# Arm.net
KiCad netlist of a schematic drawn in EAGLE
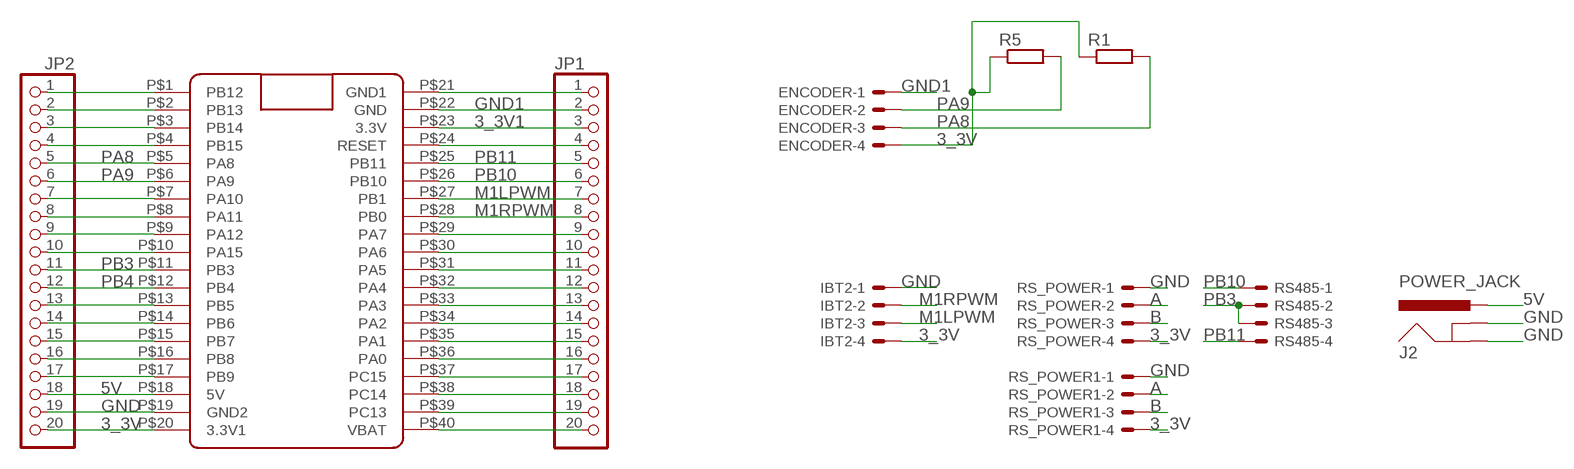
[diagram p0: schematic, sheet 1]

(export (version "E")
  (design (tool "Eeschema 10.0.6"))
  (components
    (comp (ref "ENCODER")
      (value "JST-XH-04-PIN-LONG-PAD")
      (footprint "eagle-import:JST-XH-04-PACKAGE-LONG-PAD")
      (libsource (lib "eagle-import") (part "JST-XH-04-PIN-LONG-PAD"))
    )
    (comp (ref "IBT2")
      (value "JST-XH-04-PIN-LONG-PAD")
      (footprint "eagle-import:JST-XH-04-PACKAGE-LONG-PAD")
      (libsource (lib "eagle-import") (part "JST-XH-04-PIN-LONG-PAD"))
    )
    (comp (ref "J2")
      (value "POWER_JACK")
      (footprint "eagle-import:POWER_JACK")
      (fields (field (name "MPN") "PJ-202A"))
      (libsource (lib "eagle-import") (part "POWER_JACK"))
    )
    (comp (ref "JP1")
      (value "PINHD-1X20")
      (footprint "eagle-import:1X20")
      (libsource (lib "eagle-import") (part "PINHD-1X20"))
    )
    (comp (ref "JP2")
      (value "PINHD-1X20")
      (footprint "eagle-import:1X20")
      (libsource (lib "eagle-import") (part "PINHD-1X20"))
    )
    (comp (ref "R1")
      (value "R-EU_0207/10")
      (footprint "eagle-import:0207_10")
      (libsource (lib "eagle-import") (part "R-EU_0207/10"))
    )
    (comp (ref "R5")
      (value "R-EU_0207/10")
      (footprint "eagle-import:0207_10")
      (libsource (lib "eagle-import") (part "R-EU_0207/10"))
    )
    (comp (ref "RS485")
      (value "JST-XH-04-PIN-LONG-PAD")
      (footprint "eagle-import:JST-XH-04-PACKAGE-LONG-PAD")
      (libsource (lib "eagle-import") (part "JST-XH-04-PIN-LONG-PAD"))
    )
    (comp (ref "RS_POWER")
      (value "JST-XH-04-PIN-LONG-PAD")
      (footprint "eagle-import:JST-XH-04-PACKAGE-LONG-PAD")
      (libsource (lib "eagle-import") (part "JST-XH-04-PIN-LONG-PAD"))
    )
    (comp (ref "RS_POWER1")
      (value "JST-XH-04-PIN-LONG-PAD")
      (footprint "eagle-import:JST-XH-04-PACKAGE-LONG-PAD")
      (libsource (lib "eagle-import") (part "JST-XH-04-PIN-LONG-PAD"))
    )
    (comp (ref "U$1")
      (value "BLUE_PILL")
      (footprint "eagle-import:BLUE_PILL")
      (libsource (lib "eagle-import") (part "BLUE_PILL"))
    )
  )
  (nets
    (net (code "1") (name "/3_3V") (class "Default")
      (node (ref "ENCODER") (pin "4") (pinfunction "S_4") (pintype "passive"))
      (node (ref "IBT2") (pin "4") (pinfunction "S_4") (pintype "passive"))
      (node (ref "JP2") (pin "20") (pinfunction "20_20") (pintype "passive"))
      (node (ref "R1") (pin "1") (pinfunction "1_1") (pintype "passive"))
      (node (ref "R5") (pin "1") (pinfunction "1_1") (pintype "passive"))
      (node (ref "RS_POWER") (pin "4") (pinfunction "S_4") (pintype "passive"))
      (node (ref "RS_POWER1") (pin "4") (pinfunction "S_4") (pintype "passive"))
      (node (ref "U$1") (pin "P$20") (pinfunction "3.3V1_P$20") (pintype "bidirectional"))
    )
    (net (code "2") (name "/3_3V1") (class "Default")
      (node (ref "JP1") (pin "3") (pinfunction "3_3") (pintype "passive"))
      (node (ref "U$1") (pin "P$23") (pinfunction "3.3V_P$23") (pintype "bidirectional"))
    )
    (net (code "3") (name "/5V") (class "Default")
      (node (ref "J2") (pin "PWR") (pinfunction "PWR_PWR") (pintype "bidirectional"))
      (node (ref "JP2") (pin "18") (pinfunction "18_18") (pintype "passive"))
      (node (ref "U$1") (pin "P$18") (pinfunction "5V_P$18") (pintype "bidirectional"))
    )
    (net (code "4") (name "/A") (class "Default")
      (node (ref "RS_POWER") (pin "2") (pinfunction "S_2") (pintype "passive"))
      (node (ref "RS_POWER1") (pin "2") (pinfunction "S_2") (pintype "passive"))
    )
    (net (code "5") (name "/B") (class "Default")
      (node (ref "RS_POWER") (pin "3") (pinfunction "S_3") (pintype "passive"))
      (node (ref "RS_POWER1") (pin "3") (pinfunction "S_3") (pintype "passive"))
    )
    (net (code "6") (name "/GND") (class "Default")
      (node (ref "IBT2") (pin "1") (pinfunction "S_1") (pintype "passive"))
      (node (ref "J2") (pin "GNDBREAK") (pinfunction "GNDBREAK_GNDBREAK") (pintype "bidirectional"))
      (node (ref "JP2") (pin "19") (pinfunction "19_19") (pintype "passive"))
      (node (ref "RS_POWER") (pin "1") (pinfunction "S_1") (pintype "passive"))
      (node (ref "RS_POWER1") (pin "1") (pinfunction "S_1") (pintype "passive"))
      (node (ref "U$1") (pin "P$19") (pinfunction "GND2_P$19") (pintype "bidirectional"))
    )
    (net (code "7") (name "/GND1") (class "Default")
      (node (ref "ENCODER") (pin "1") (pinfunction "S_1") (pintype "passive"))
      (node (ref "JP1") (pin "2") (pinfunction "2_2") (pintype "passive"))
      (node (ref "U$1") (pin "P$22") (pinfunction "GND_P$22") (pintype "bidirectional"))
    )
    (net (code "8") (name "/M1LPWM") (class "Default")
      (node (ref "IBT2") (pin "3") (pinfunction "S_3") (pintype "passive"))
      (node (ref "JP1") (pin "7") (pinfunction "7_7") (pintype "passive"))
      (node (ref "U$1") (pin "P$27") (pinfunction "PB1_P$27") (pintype "bidirectional"))
    )
    (net (code "9") (name "/M1RPWM") (class "Default")
      (node (ref "IBT2") (pin "2") (pinfunction "S_2") (pintype "passive"))
      (node (ref "JP1") (pin "8") (pinfunction "8_8") (pintype "passive"))
      (node (ref "U$1") (pin "P$28") (pinfunction "PB0_P$28") (pintype "bidirectional"))
    )
    (net (code "10") (name "/PA8") (class "Default")
      (node (ref "ENCODER") (pin "3") (pinfunction "S_3") (pintype "passive"))
      (node (ref "JP2") (pin "5") (pinfunction "5_5") (pintype "passive"))
      (node (ref "R1") (pin "2") (pinfunction "2_2") (pintype "passive"))
      (node (ref "U$1") (pin "P$5") (pinfunction "PA8_P$5") (pintype "bidirectional"))
    )
    (net (code "11") (name "/PA9") (class "Default")
      (node (ref "ENCODER") (pin "2") (pinfunction "S_2") (pintype "passive"))
      (node (ref "JP2") (pin "6") (pinfunction "6_6") (pintype "passive"))
      (node (ref "R5") (pin "2") (pinfunction "2_2") (pintype "passive"))
      (node (ref "U$1") (pin "P$6") (pinfunction "PA9_P$6") (pintype "bidirectional"))
    )
    (net (code "12") (name "/PB3") (class "Default")
      (node (ref "JP2") (pin "11") (pinfunction "11_11") (pintype "passive"))
      (node (ref "RS485") (pin "2") (pinfunction "S_2") (pintype "passive"))
      (node (ref "RS485") (pin "3") (pinfunction "S_3") (pintype "passive"))
      (node (ref "U$1") (pin "P$11") (pinfunction "PB3_P$11") (pintype "bidirectional"))
    )
    (net (code "13") (name "/PB4") (class "Default")
      (node (ref "JP2") (pin "12") (pinfunction "12_12") (pintype "passive"))
      (node (ref "U$1") (pin "P$12") (pinfunction "PB4_P$12") (pintype "bidirectional"))
    )
    (net (code "14") (name "/PB10") (class "Default")
      (node (ref "JP1") (pin "6") (pinfunction "6_6") (pintype "passive"))
      (node (ref "RS485") (pin "1") (pinfunction "S_1") (pintype "passive"))
      (node (ref "U$1") (pin "P$26") (pinfunction "PB10_P$26") (pintype "bidirectional"))
    )
    (net (code "15") (name "/PB11") (class "Default")
      (node (ref "JP1") (pin "5") (pinfunction "5_5") (pintype "passive"))
      (node (ref "RS485") (pin "4") (pinfunction "S_4") (pintype "passive"))
      (node (ref "U$1") (pin "P$25") (pinfunction "PB11_P$25") (pintype "bidirectional"))
    )
    (net (code "16") (name "Net-(U$1-GND1)") (class "Default")
      (node (ref "JP1") (pin "1") (pinfunction "1_1") (pintype "passive"))
      (node (ref "U$1") (pin "P$21") (pinfunction "GND1_P$21") (pintype "power_in"))
    )
    (net (code "17") (name "Net-(U$1-PA0)") (class "Default")
      (node (ref "JP1") (pin "16") (pinfunction "16_16") (pintype "passive"))
      (node (ref "U$1") (pin "P$36") (pinfunction "PA0_P$36") (pintype "bidirectional"))
    )
    (net (code "18") (name "Net-(U$1-PA1)") (class "Default")
      (node (ref "JP1") (pin "15") (pinfunction "15_15") (pintype "passive"))
      (node (ref "U$1") (pin "P$35") (pinfunction "PA1_P$35") (pintype "bidirectional"))
    )
    (net (code "19") (name "Net-(U$1-PA2)") (class "Default")
      (node (ref "JP1") (pin "14") (pinfunction "14_14") (pintype "passive"))
      (node (ref "U$1") (pin "P$34") (pinfunction "PA2_P$34") (pintype "bidirectional"))
    )
    (net (code "20") (name "Net-(U$1-PA3)") (class "Default")
      (node (ref "JP1") (pin "13") (pinfunction "13_13") (pintype "passive"))
      (node (ref "U$1") (pin "P$33") (pinfunction "PA3_P$33") (pintype "bidirectional"))
    )
    (net (code "21") (name "Net-(U$1-PA4)") (class "Default")
      (node (ref "JP1") (pin "12") (pinfunction "12_12") (pintype "passive"))
      (node (ref "U$1") (pin "P$32") (pinfunction "PA4_P$32") (pintype "bidirectional"))
    )
    (net (code "22") (name "Net-(U$1-PA5)") (class "Default")
      (node (ref "JP1") (pin "11") (pinfunction "11_11") (pintype "passive"))
      (node (ref "U$1") (pin "P$31") (pinfunction "PA5_P$31") (pintype "bidirectional"))
    )
    (net (code "23") (name "Net-(U$1-PA6)") (class "Default")
      (node (ref "JP1") (pin "10") (pinfunction "10_10") (pintype "passive"))
      (node (ref "U$1") (pin "P$30") (pinfunction "PA6_P$30") (pintype "bidirectional"))
    )
    (net (code "24") (name "Net-(U$1-PA7)") (class "Default")
      (node (ref "JP1") (pin "9") (pinfunction "9_9") (pintype "passive"))
      (node (ref "U$1") (pin "P$29") (pinfunction "PA7_P$29") (pintype "bidirectional"))
    )
    (net (code "25") (name "Net-(U$1-PA10)") (class "Default")
      (node (ref "JP2") (pin "7") (pinfunction "7_7") (pintype "passive"))
      (node (ref "U$1") (pin "P$7") (pinfunction "PA10_P$7") (pintype "bidirectional"))
    )
    (net (code "26") (name "Net-(U$1-PA11)") (class "Default")
      (node (ref "JP2") (pin "8") (pinfunction "8_8") (pintype "passive"))
      (node (ref "U$1") (pin "P$8") (pinfunction "PA11_P$8") (pintype "bidirectional"))
    )
    (net (code "27") (name "Net-(U$1-PA12)") (class "Default")
      (node (ref "JP2") (pin "9") (pinfunction "9_9") (pintype "passive"))
      (node (ref "U$1") (pin "P$9") (pinfunction "PA12_P$9") (pintype "bidirectional"))
    )
    (net (code "28") (name "Net-(U$1-PA15)") (class "Default")
      (node (ref "JP2") (pin "10") (pinfunction "10_10") (pintype "passive"))
      (node (ref "U$1") (pin "P$10") (pinfunction "PA15_P$10") (pintype "bidirectional"))
    )
    (net (code "29") (name "Net-(U$1-PB5)") (class "Default")
      (node (ref "JP2") (pin "13") (pinfunction "13_13") (pintype "passive"))
      (node (ref "U$1") (pin "P$13") (pinfunction "PB5_P$13") (pintype "bidirectional"))
    )
    (net (code "30") (name "Net-(U$1-PB6)") (class "Default")
      (node (ref "JP2") (pin "14") (pinfunction "14_14") (pintype "passive"))
      (node (ref "U$1") (pin "P$14") (pinfunction "PB6_P$14") (pintype "bidirectional"))
    )
    (net (code "31") (name "Net-(U$1-PB7)") (class "Default")
      (node (ref "JP2") (pin "15") (pinfunction "15_15") (pintype "passive"))
      (node (ref "U$1") (pin "P$15") (pinfunction "PB7_P$15") (pintype "bidirectional"))
    )
    (net (code "32") (name "Net-(U$1-PB8)") (class "Default")
      (node (ref "JP2") (pin "16") (pinfunction "16_16") (pintype "passive"))
      (node (ref "U$1") (pin "P$16") (pinfunction "PB8_P$16") (pintype "bidirectional"))
    )
    (net (code "33") (name "Net-(U$1-PB9)") (class "Default")
      (node (ref "JP2") (pin "17") (pinfunction "17_17") (pintype "passive"))
      (node (ref "U$1") (pin "P$17") (pinfunction "PB9_P$17") (pintype "bidirectional"))
    )
    (net (code "34") (name "Net-(U$1-PB12)") (class "Default")
      (node (ref "JP2") (pin "1") (pinfunction "1_1") (pintype "passive"))
      (node (ref "U$1") (pin "P$1") (pinfunction "PB12_P$1") (pintype "bidirectional"))
    )
    (net (code "35") (name "Net-(U$1-PB13)") (class "Default")
      (node (ref "JP2") (pin "2") (pinfunction "2_2") (pintype "passive"))
      (node (ref "U$1") (pin "P$2") (pinfunction "PB13_P$2") (pintype "bidirectional"))
    )
    (net (code "36") (name "Net-(U$1-PB14)") (class "Default")
      (node (ref "JP2") (pin "3") (pinfunction "3_3") (pintype "passive"))
      (node (ref "U$1") (pin "P$3") (pinfunction "PB14_P$3") (pintype "bidirectional"))
    )
    (net (code "37") (name "Net-(U$1-PB15)") (class "Default")
      (node (ref "JP2") (pin "4") (pinfunction "4_4") (pintype "passive"))
      (node (ref "U$1") (pin "P$4") (pinfunction "PB15_P$4") (pintype "bidirectional"))
    )
    (net (code "38") (name "Net-(U$1-PC13)") (class "Default")
      (node (ref "JP1") (pin "19") (pinfunction "19_19") (pintype "passive"))
      (node (ref "U$1") (pin "P$39") (pinfunction "PC13_P$39") (pintype "bidirectional"))
    )
    (net (code "39") (name "Net-(U$1-PC14)") (class "Default")
      (node (ref "JP1") (pin "18") (pinfunction "18_18") (pintype "passive"))
      (node (ref "U$1") (pin "P$38") (pinfunction "PC14_P$38") (pintype "bidirectional"))
    )
    (net (code "40") (name "Net-(U$1-PC15)") (class "Default")
      (node (ref "JP1") (pin "17") (pinfunction "17_17") (pintype "passive"))
      (node (ref "U$1") (pin "P$37") (pinfunction "PC15_P$37") (pintype "bidirectional"))
    )
    (net (code "41") (name "Net-(U$1-RESET)") (class "Default")
      (node (ref "JP1") (pin "4") (pinfunction "4_4") (pintype "passive"))
      (node (ref "U$1") (pin "P$24") (pinfunction "RESET_P$24") (pintype "bidirectional"))
    )
    (net (code "42") (name "Net-(U$1-VBAT)") (class "Default")
      (node (ref "JP1") (pin "20") (pinfunction "20_20") (pintype "passive"))
      (node (ref "U$1") (pin "P$40") (pinfunction "VBAT_P$40") (pintype "bidirectional"))
    )
    (net (code "43") (name "unconnected-(J2-PadGND)") (class "Default")
      (node (ref "J2") (pin "GND") (pinfunction "GND_GND") (pintype "bidirectional"))
    )
  )
)
